# SH6_-_BRUSHED_MOTOR_CONTROLLER.net
KiCad netlist of a schematic drawn in Altium Designer
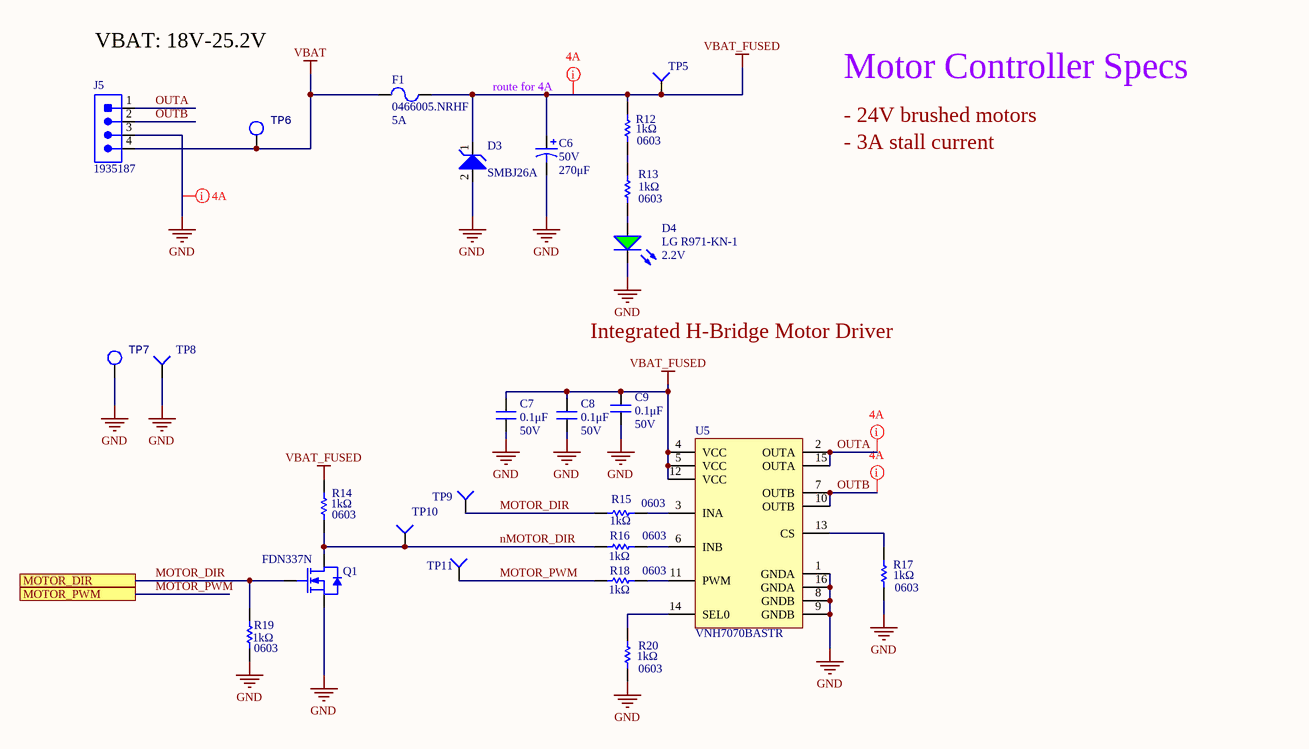
[diagram p0: SH6 - BRUSHED MOTOR CONTROLLER.SchDoc]

(export (version "E")
  (design (tool "Eeschema 10.0.6"))
  (components
    (comp (ref "C6")
      (value "270μF")
      (footprint "RADIAL_PANASONIC_G")
      (description "CAP ALUM 270uF 50VDC 20% SMD")
      (fields (field (name "VOLTAGE RATING") "50V") (field (name "Comment") "CAP_270uF_50V_ALUM"))
      (libsource (lib "UWRT_Schematic_Library_2020") (part "CAP_270uF_50V_ALUM"))
    )
    (comp (ref "C7")
      (value "0.1μF")
      (footprint "CAP0603")
      (description "CAP CER 0.1UF 50V X7R 0603")
      (fields (field (name "VOLTAGE RATING") "50V") (field (name "Comment") "CAP_0.1uF_50V_0603"))
      (libsource (lib "UWRT_Schematic_Library_2020") (part "CAP_0.1uF_50V_0603"))
    )
    (comp (ref "C8")
      (value "0.1μF")
      (footprint "CAP0603")
      (description "CAP CER 0.1UF 50V X7R 0603")
      (fields (field (name "VOLTAGE RATING") "50V") (field (name "Comment") "CAP_0.1uF_50V_0603"))
      (libsource (lib "UWRT_Schematic_Library_2020") (part "CAP_0.1uF_50V_0603"))
    )
    (comp (ref "C9")
      (value "0.1μF")
      (footprint "CAP0603")
      (description "CAP CER 0.1UF 50V X7R 0603")
      (fields (field (name "VOLTAGE RATING") "50V") (field (name "Comment") "CAP_0.1uF_50V_0603"))
      (libsource (lib "UWRT_Schematic_Library_2020") (part "CAP_0.1uF_50V_0603"))
    )
    (comp (ref "D3")
      (value "TVS_DIODE_UNIDIR_26V")
      (footprint "TVS_DIODE_UNIDIRECTIONAL_SMB")
      (description "TVS DIODE 26V 42.1V SMB")
      (fields (field (name "MANUFACTURER PART NUMBER 1") "SMBJ26A"))
      (libsource (lib "UWRT_Schematic_Library_2020") (part "TVS_DIODE_UNIDIR_26V"))
    )
    (comp (ref "D4")
      (value "LED_GREEN")
      (footprint "LED_0805_GREEN")
      (description "LED GREEN DIFFUSED 0805 SMD")
      (fields
        (field (name "FORWARD VOLTAGE DROP") "2.2V")
        (field (name "MANUFACTURER PART NUMBER 1") "LG R971-KN-1")
      )
      (libsource (lib "UWRT_Schematic_Library_2020") (part "LED_GREEN"))
    )
    (comp (ref "F1")
      (value "FUSE_5A_1206")
      (footprint "FUSE_1206")
      (description "FUSE BOARD MNT 5A 32VAC/VDC 1206")
      (fields (field (name "MANUFACTURER PART NUMBER 1") "0466005.NRHF") (field (name "CURRENT RATING") "5A"))
      (libsource (lib "UWRT_Schematic_Library_2020") (part "FUSE_5A_1206"))
    )
    (comp (ref "J5")
      (value "CON_4M_TERM")
      (footprint "1935187")
      (description "TERM BLK 4POS SIDE ENTRY 5MM PCB")
      (fields (field (name "MANUFACTURER PART NUMBER 1") "1935187"))
      (libsource (lib "UWRT_Schematic_Library_2020") (part "CON_4M_TERM"))
    )
    (comp (ref "Q1")
      (value "NMOS_30V_2.2A")
      (footprint "NMOS_SSOT-3")
      (description "MOSFET N-CH 30V 2.2A SUPERSOT3")
      (fields (field (name "MANUFACTURER PART NUMBER 1") "FDN337N"))
      (libsource (lib "UWRT_Schematic_Library_2020") (part "NMOS_30V_2.2A"))
    )
    (comp (ref "R12")
      (value "1kΩ")
      (footprint "RESC0603")
      (description "RES 1K OHM 5% 1/10W 0603")
      (fields (field (name "PACKAGE/FOOTPRINT") "0603") (field (name "Comment") "RES_1kΩ_0603_5%"))
      (libsource (lib "UWRT_Schematic_Library_2020") (part "RES_1kΩ_0603_5%"))
    )
    (comp (ref "R13")
      (value "1kΩ")
      (footprint "RESC0603")
      (description "RES 1K OHM 5% 1/10W 0603")
      (fields (field (name "PACKAGE/FOOTPRINT") "0603") (field (name "Comment") "RES_1kΩ_0603_5%"))
      (libsource (lib "UWRT_Schematic_Library_2020") (part "RES_1kΩ_0603_5%"))
    )
    (comp (ref "R14")
      (value "1kΩ")
      (footprint "RESC0603")
      (description "RES 1K OHM 5% 1/10W 0603")
      (fields (field (name "PACKAGE/FOOTPRINT") "0603") (field (name "Comment") "RES_1kΩ_0603_5%"))
      (libsource (lib "UWRT_Schematic_Library_2020") (part "RES_1kΩ_0603_5%"))
    )
    (comp (ref "R15")
      (value "1kΩ")
      (footprint "RESC0603")
      (description "RES 1K OHM 5% 1/10W 0603")
      (fields (field (name "PACKAGE/FOOTPRINT") "0603") (field (name "Comment") "RES_1kΩ_0603_5%"))
      (libsource (lib "UWRT_Schematic_Library_2020") (part "RES_1kΩ_0603_5%"))
    )
    (comp (ref "R16")
      (value "1kΩ")
      (footprint "RESC0603")
      (description "RES 1K OHM 5% 1/10W 0603")
      (fields (field (name "PACKAGE/FOOTPRINT") "0603") (field (name "Comment") "RES_1kΩ_0603_5%"))
      (libsource (lib "UWRT_Schematic_Library_2020") (part "RES_1kΩ_0603_5%"))
    )
    (comp (ref "R17")
      (value "1kΩ")
      (footprint "RESC0603")
      (description "RES 1K OHM 5% 1/10W 0603")
      (fields (field (name "PACKAGE/FOOTPRINT") "0603") (field (name "Comment") "RES_1kΩ_0603_5%"))
      (libsource (lib "UWRT_Schematic_Library_2020") (part "RES_1kΩ_0603_5%"))
    )
    (comp (ref "R18")
      (value "1kΩ")
      (footprint "RESC0603")
      (description "RES 1K OHM 5% 1/10W 0603")
      (fields (field (name "PACKAGE/FOOTPRINT") "0603") (field (name "Comment") "RES_1kΩ_0603_5%"))
      (libsource (lib "UWRT_Schematic_Library_2020") (part "RES_1kΩ_0603_5%"))
    )
    (comp (ref "R19")
      (value "1kΩ")
      (footprint "RESC0603")
      (description "RES 1K OHM 5% 1/10W 0603")
      (fields (field (name "PACKAGE/FOOTPRINT") "0603") (field (name "Comment") "RES_1kΩ_0603_5%"))
      (libsource (lib "UWRT_Schematic_Library_2020") (part "RES_1kΩ_0603_5%"))
    )
    (comp (ref "R20")
      (value "1kΩ")
      (footprint "RESC0603")
      (description "RES 1K OHM 5% 1/10W 0603")
      (fields (field (name "PACKAGE/FOOTPRINT") "0603") (field (name "Comment") "RES_1kΩ_0603_5%"))
      (libsource (lib "UWRT_Schematic_Library_2020") (part "RES_1kΩ_0603_5%"))
    )
    (comp (ref "TP5")
      (value "TESTPOINT_1MM_CIRCLE")
      (footprint "TESTPOINT_CIRCLE_1MM")
      (description "TESTPOINT 1MM CIRCLE")
      (libsource (lib "UWRT_Schematic_Library_2020") (part "TESTPOINT_1MM_CIRCLE"))
    )
    (comp (ref "TP6")
      (value "TESTPOINT_LOOP")
      (footprint "TESTPOINT_LOOP")
      (description "TESTPOINT THRUHOLE")
      (libsource (lib "UWRT_Schematic_Library_2020") (part "TESTPOINT_LOOP"))
    )
    (comp (ref "TP7")
      (value "TESTPOINT_LOOP")
      (footprint "TESTPOINT_LOOP")
      (description "TESTPOINT THRUHOLE")
      (libsource (lib "UWRT_Schematic_Library_2020") (part "TESTPOINT_LOOP"))
    )
    (comp (ref "TP8")
      (value "TESTPOINT_1MM_SQUARE")
      (footprint "TESTPOINT_SQUARE_1MM")
      (description "TESTPOINT 1MM SQUARE")
      (libsource (lib "UWRT_Schematic_Library_2020") (part "TESTPOINT_1MM_SQUARE"))
    )
    (comp (ref "TP9")
      (value "TESTPOINT_1MM_CIRCLE")
      (footprint "TESTPOINT_CIRCLE_1MM")
      (description "TESTPOINT 1MM CIRCLE")
      (libsource (lib "UWRT_Schematic_Library_2020") (part "TESTPOINT_1MM_CIRCLE"))
    )
    (comp (ref "TP10")
      (value "TESTPOINT_1MM_CIRCLE")
      (footprint "TESTPOINT_CIRCLE_1MM")
      (description "TESTPOINT 1MM CIRCLE")
      (libsource (lib "UWRT_Schematic_Library_2020") (part "TESTPOINT_1MM_CIRCLE"))
    )
    (comp (ref "TP11")
      (value "TESTPOINT_1MM_CIRCLE")
      (footprint "TESTPOINT_CIRCLE_1MM")
      (description "TESTPOINT 1MM CIRCLE")
      (libsource (lib "UWRT_Schematic_Library_2020") (part "TESTPOINT_1MM_CIRCLE"))
    )
    (comp (ref "U5")
      (value "IC_MOTOR_DRIVER_ST")
      (footprint "SO-16N")
      (description "IC MOTOR DRIVER 4V-28V 16SOIC")
      (fields (field (name "MANUFACTURER PART NUMBER 1") "VNH7070BASTR"))
      (libsource (lib "UWRT_Schematic_Library_2020") (part "IC_MOTOR_DRIVER_ST"))
    )
  )
  (nets
    (net (code "1") (name "/MOTOR_DIR") (class "Default")
      (node (ref "Q1") (pin "1") (pinfunction "GATE_1") (pintype "passive"))
      (node (ref "R15") (pin "1") (pinfunction "1_1") (pintype "passive"))
      (node (ref "R19") (pin "2") (pinfunction "2_2") (pintype "passive"))
      (node (ref "TP9") (pin "1") (pinfunction "=value_1") (pintype "passive"))
    )
    (net (code "2") (name "/MOTOR_PWM") (class "Default")
      (node (ref "R18") (pin "1") (pinfunction "1_1") (pintype "passive"))
      (node (ref "TP11") (pin "1") (pinfunction "=value_1") (pintype "passive"))
    )
    (net (code "3") (name "/OUTA") (class "Default")
      (node (ref "J5") (pin "1") (pinfunction "1_1") (pintype "passive"))
      (node (ref "U5") (pin "15") (pinfunction "OUTA_15") (pintype "passive"))
      (node (ref "U5") (pin "2") (pinfunction "OUTA_2") (pintype "passive"))
    )
    (net (code "4") (name "/OUTB") (class "Default")
      (node (ref "J5") (pin "2") (pinfunction "2_2") (pintype "passive"))
      (node (ref "U5") (pin "10") (pinfunction "OUTB_10") (pintype "passive"))
      (node (ref "U5") (pin "7") (pinfunction "OUTB_7") (pintype "passive"))
    )
    (net (code "5") (name "/nMOTOR_DIR") (class "Default")
      (node (ref "Q1") (pin "3") (pinfunction "DRAIN_3") (pintype "passive"))
      (node (ref "R14") (pin "1") (pinfunction "1_1") (pintype "passive"))
      (node (ref "R16") (pin "1") (pinfunction "1_1") (pintype "passive"))
      (node (ref "TP10") (pin "1") (pinfunction "=value_1") (pintype "passive"))
    )
    (net (code "6") (name "GND") (class "Default")
      (node (ref "C6") (pin "2") (pinfunction "2_2") (pintype "passive"))
      (node (ref "C7") (pin "1") (pinfunction "1_1") (pintype "passive"))
      (node (ref "C8") (pin "1") (pinfunction "1_1") (pintype "passive"))
      (node (ref "C9") (pin "2") (pinfunction "2_2") (pintype "passive"))
      (node (ref "D3") (pin "2") (pinfunction "Anode_2") (pintype "passive"))
      (node (ref "D4") (pin "2") (pinfunction "K_2") (pintype "passive"))
      (node (ref "J5") (pin "3") (pinfunction "3_3") (pintype "passive"))
      (node (ref "Q1") (pin "2") (pinfunction "SOURCE_2") (pintype "passive"))
      (node (ref "R17") (pin "1") (pinfunction "1_1") (pintype "passive"))
      (node (ref "R19") (pin "1") (pinfunction "1_1") (pintype "passive"))
      (node (ref "R20") (pin "1") (pinfunction "1_1") (pintype "passive"))
      (node (ref "TP7") (pin "1") (pintype "passive"))
      (node (ref "TP8") (pin "1") (pinfunction "=value_1") (pintype "passive"))
      (node (ref "U5") (pin "1") (pinfunction "GNDA_1") (pintype "power_in"))
      (node (ref "U5") (pin "16") (pinfunction "GNDA_16") (pintype "power_in"))
      (node (ref "U5") (pin "8") (pinfunction "GNDB_8") (pintype "power_in"))
      (node (ref "U5") (pin "9") (pinfunction "GNDB_9") (pintype "power_in"))
    )
    (net (code "7") (name "Net-(D4-A)") (class "Default")
      (node (ref "D4") (pin "1") (pinfunction "A_1") (pintype "passive"))
      (node (ref "R13") (pin "1") (pinfunction "1_1") (pintype "passive"))
    )
    (net (code "8") (name "Net-(R12-Pad1)") (class "Default")
      (node (ref "R12") (pin "1") (pinfunction "1_1") (pintype "passive"))
      (node (ref "R13") (pin "2") (pinfunction "2_2") (pintype "passive"))
    )
    (net (code "9") (name "Net-(U5-CS)") (class "Default")
      (node (ref "R17") (pin "2") (pinfunction "2_2") (pintype "passive"))
      (node (ref "U5") (pin "13") (pinfunction "CS_13") (pintype "passive"))
    )
    (net (code "10") (name "Net-(U5-INA)") (class "Default")
      (node (ref "R15") (pin "2") (pinfunction "2_2") (pintype "passive"))
      (node (ref "U5") (pin "3") (pinfunction "INA_3") (pintype "passive"))
    )
    (net (code "11") (name "Net-(U5-INB)") (class "Default")
      (node (ref "R16") (pin "2") (pinfunction "2_2") (pintype "passive"))
      (node (ref "U5") (pin "6") (pinfunction "INB_6") (pintype "passive"))
    )
    (net (code "12") (name "Net-(U5-PWM)") (class "Default")
      (node (ref "R18") (pin "2") (pinfunction "2_2") (pintype "passive"))
      (node (ref "U5") (pin "11") (pinfunction "PWM_11") (pintype "passive"))
    )
    (net (code "13") (name "Net-(U5-SEL0)") (class "Default")
      (node (ref "R20") (pin "2") (pinfunction "2_2") (pintype "passive"))
      (node (ref "U5") (pin "14") (pinfunction "SEL0_14") (pintype "passive"))
    )
    (net (code "14") (name "VBAT") (class "Default")
      (node (ref "F1") (pin "1") (pinfunction "1_1") (pintype "passive"))
      (node (ref "J5") (pin "4") (pinfunction "4_4") (pintype "passive"))
      (node (ref "TP6") (pin "1") (pintype "passive"))
    )
    (net (code "15") (name "VBAT_FUSED") (class "Default")
      (node (ref "C6") (pin "1") (pinfunction "1_1") (pintype "passive"))
      (node (ref "C7") (pin "2") (pinfunction "2_2") (pintype "passive"))
      (node (ref "C8") (pin "2") (pinfunction "2_2") (pintype "passive"))
      (node (ref "C9") (pin "1") (pinfunction "1_1") (pintype "passive"))
      (node (ref "D3") (pin "1") (pinfunction "Cathode_1") (pintype "passive"))
      (node (ref "F1") (pin "2") (pinfunction "2_2") (pintype "passive"))
      (node (ref "R12") (pin "2") (pinfunction "2_2") (pintype "passive"))
      (node (ref "R14") (pin "2") (pinfunction "2_2") (pintype "passive"))
      (node (ref "TP5") (pin "1") (pinfunction "=value_1") (pintype "passive"))
      (node (ref "U5") (pin "12") (pinfunction "VCC_12") (pintype "power_in"))
      (node (ref "U5") (pin "4") (pinfunction "VCC_4") (pintype "power_in"))
      (node (ref "U5") (pin "5") (pinfunction "VCC_5") (pintype "power_in"))
    )
  )
)
